# TSL45315-Breakout_v12.net
KiCad netlist of a schematic drawn in EAGLE
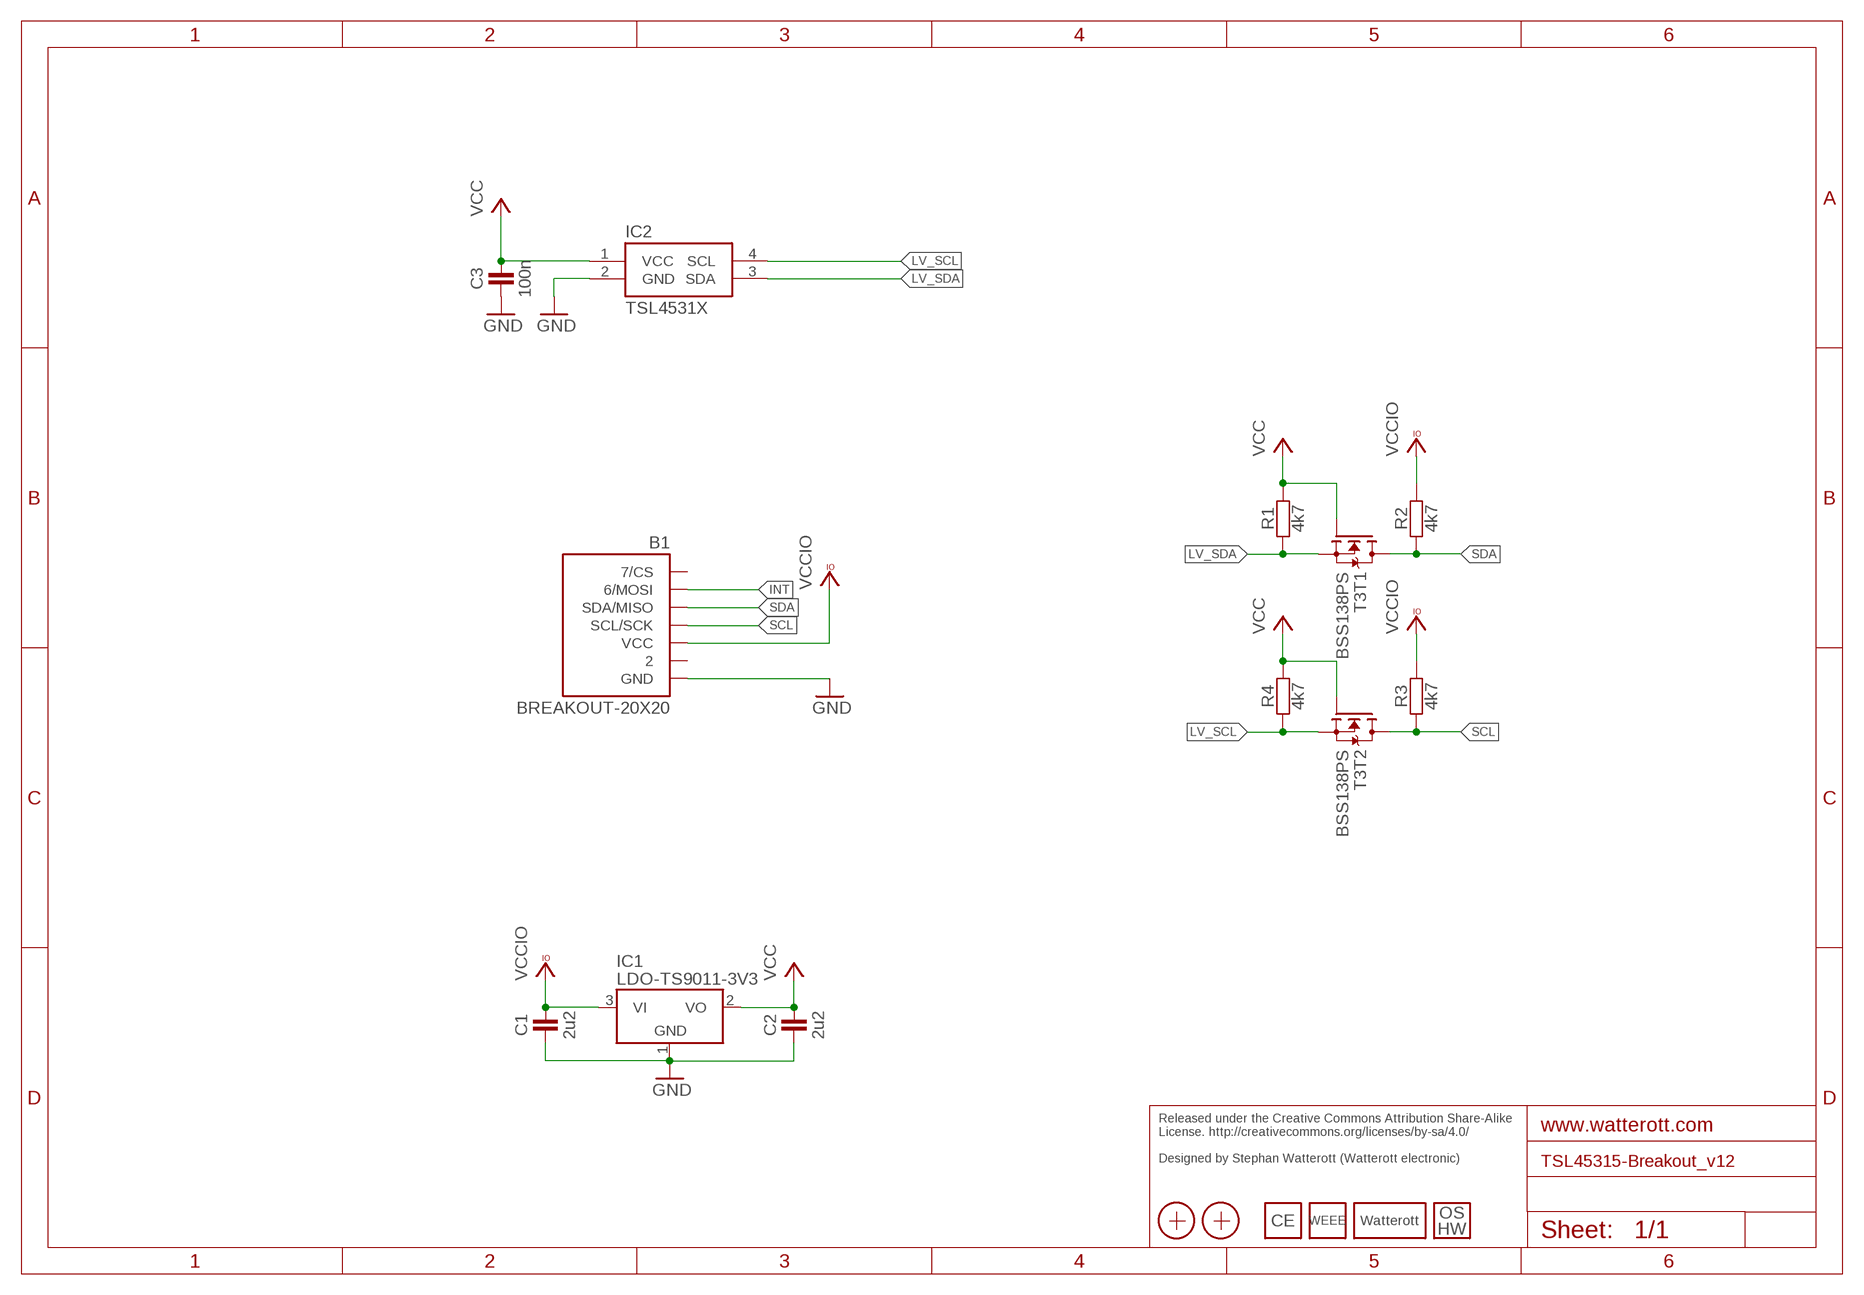
[diagram p0: schematic, sheet 1]

(export (version "E")
  (design (tool "Eeschema 10.0.6"))
  (components
    (comp (ref "B1")
      (value "BREAKOUT-20X20")
      (footprint "eagle-import:BREAKOUT-20X20")
      (libsource (lib "eagle-import") (part "BREAKOUT-20X20"))
    )
    (comp (ref "C1")
      (value "2u2")
      (footprint "eagle-import:C0402")
      (libsource (lib "eagle-import") (part "CAPACITOR-0402"))
    )
    (comp (ref "C2")
      (value "2u2")
      (footprint "eagle-import:C0402")
      (libsource (lib "eagle-import") (part "CAPACITOR-0402"))
    )
    (comp (ref "C3")
      (value "100n")
      (footprint "eagle-import:C0402")
      (libsource (lib "eagle-import") (part "CAPACITOR-0402"))
    )
    (comp (ref "IC1")
      (value "LDO-TS9011-3V3")
      (footprint "eagle-import:SOT23")
      (libsource (lib "eagle-import") (part "LDO-TS9011-3V3"))
    )
    (comp (ref "IC2")
      (value "TSL4531X")
      (footprint "eagle-import:AMS_CL")
      (libsource (lib "eagle-import") (part "TSL4531X"))
    )
    (comp (ref "LOGO3")
      (value "LOGO_WEEE-4")
      (footprint "eagle-import:WEEE_4MM")
      (libsource (lib "eagle-import") (part "LOGO_WEEE-4"))
    )
    (comp (ref "LOGO4")
      (value "LOGO_CE-4")
      (footprint "eagle-import:CE_4MM")
      (libsource (lib "eagle-import") (part "LOGO_CE-4"))
    )
    (comp (ref "LOGO5")
      (value "LOGO_SPARK-4")
      (footprint "eagle-import:SPARK_4MM")
      (libsource (lib "eagle-import") (part "LOGO_SPARK-4"))
    )
    (comp (ref "LOGO6")
      (value "LOGO_OSHW-2")
      (footprint "eagle-import:OSHW_2MM")
      (libsource (lib "eagle-import") (part "LOGO_OSHW-2"))
    )
    (comp (ref "R1")
      (value "4k7")
      (footprint "eagle-import:C0402")
      (libsource (lib "eagle-import") (part "RESISTOR-0402"))
    )
    (comp (ref "R2")
      (value "4k7")
      (footprint "eagle-import:C0402")
      (libsource (lib "eagle-import") (part "RESISTOR-0402"))
    )
    (comp (ref "R3")
      (value "4k7")
      (footprint "eagle-import:C0402")
      (libsource (lib "eagle-import") (part "RESISTOR-0402"))
    )
    (comp (ref "R4")
      (value "4k7")
      (footprint "eagle-import:C0402")
      (libsource (lib "eagle-import") (part "RESISTOR-0402"))
    )
    (comp (ref "T3")
      (value "BSS138PS")
      (footprint "eagle-import:SOT363")
      (libsource (lib "eagle-import") (part "BSS138PS"))
    )
    (comp (ref "X1")
      (value "PASSER-07")
      (footprint "eagle-import:PASSER_07MM")
      (libsource (lib "eagle-import") (part "PASSER-07"))
    )
    (comp (ref "X2")
      (value "PASSER-07")
      (footprint "eagle-import:PASSER_07MM")
      (libsource (lib "eagle-import") (part "PASSER-07"))
    )
  )
  (nets
    (net (code "1") (name "GND") (class "Default")
      (node (ref "B1") (pin "GND") (pinfunction "GND_GND") (pintype "power_in"))
      (node (ref "C1") (pin "1") (pinfunction "1_1") (pintype "passive"))
      (node (ref "C2") (pin "1") (pinfunction "1_1") (pintype "passive"))
      (node (ref "C3") (pin "1") (pinfunction "1_1") (pintype "passive"))
      (node (ref "IC1") (pin "1") (pinfunction "GND_1") (pintype "passive"))
      (node (ref "IC2") (pin "2") (pinfunction "GND_2") (pintype "power_in"))
    )
    (net (code "2") (name "INT") (class "Default")
      (node (ref "B1") (pin "MOSI") (pinfunction "6/MOSI_MOSI") (pintype "bidirectional"))
    )
    (net (code "3") (name "LV_SCL") (class "Default")
      (node (ref "IC2") (pin "4") (pinfunction "SCL_4") (pintype "bidirectional"))
      (node (ref "R4") (pin "1") (pinfunction "1_1") (pintype "passive"))
      (node (ref "T3") (pin "4") (pinfunction "S_4") (pintype "passive"))
    )
    (net (code "4") (name "LV_SDA") (class "Default")
      (node (ref "IC2") (pin "3") (pinfunction "SDA_3") (pintype "bidirectional"))
      (node (ref "R1") (pin "1") (pinfunction "1_1") (pintype "passive"))
      (node (ref "T3") (pin "1") (pinfunction "S_1") (pintype "passive"))
    )
    (net (code "5") (name "SCL") (class "Default")
      (node (ref "B1") (pin "SCL/SCK") (pinfunction "SCL/SCK_SCL/SCK") (pintype "bidirectional"))
      (node (ref "R3") (pin "1") (pinfunction "1_1") (pintype "passive"))
      (node (ref "T3") (pin "3") (pinfunction "D_3") (pintype "passive"))
    )
    (net (code "6") (name "SDA") (class "Default")
      (node (ref "B1") (pin "SDA/MISO") (pinfunction "SDA/MISO_SDA/MISO") (pintype "bidirectional"))
      (node (ref "R2") (pin "1") (pinfunction "1_1") (pintype "passive"))
      (node (ref "T3") (pin "6") (pinfunction "D_6") (pintype "passive"))
    )
    (net (code "7") (name "VCC") (class "Default")
      (node (ref "C2") (pin "2") (pinfunction "2_2") (pintype "passive"))
      (node (ref "C3") (pin "2") (pinfunction "2_2") (pintype "passive"))
      (node (ref "IC1") (pin "2") (pinfunction "VO_2") (pintype "passive"))
      (node (ref "IC2") (pin "1") (pinfunction "VCC_1") (pintype "power_in"))
      (node (ref "R1") (pin "2") (pinfunction "2_2") (pintype "passive"))
      (node (ref "R4") (pin "2") (pinfunction "2_2") (pintype "passive"))
      (node (ref "T3") (pin "2") (pinfunction "G_2") (pintype "passive"))
      (node (ref "T3") (pin "5") (pinfunction "G_5") (pintype "passive"))
    )
    (net (code "8") (name "VCCIO") (class "Default")
      (node (ref "B1") (pin "VCC") (pinfunction "VCC_VCC") (pintype "power_in"))
      (node (ref "C1") (pin "2") (pinfunction "2_2") (pintype "passive"))
      (node (ref "IC1") (pin "3") (pinfunction "VI_3") (pintype "input"))
      (node (ref "R2") (pin "2") (pinfunction "2_2") (pintype "passive"))
      (node (ref "R3") (pin "2") (pinfunction "2_2") (pintype "passive"))
    )
    (net (code "9") (name "unconnected-(B1-7{slash}CS-PadCS)") (class "Default")
      (node (ref "B1") (pin "CS") (pinfunction "7/CS_CS") (pintype "bidirectional"))
    )
    (net (code "10") (name "unconnected-(B1-Pad2)") (class "Default")
      (node (ref "B1") (pin "2") (pinfunction "2_2") (pintype "bidirectional"))
    )
  )
)
